# SCH_Navigation_Board_CapibaraZero_2024-0.net
KiCad netlist of a schematic drawn in EasyEDA
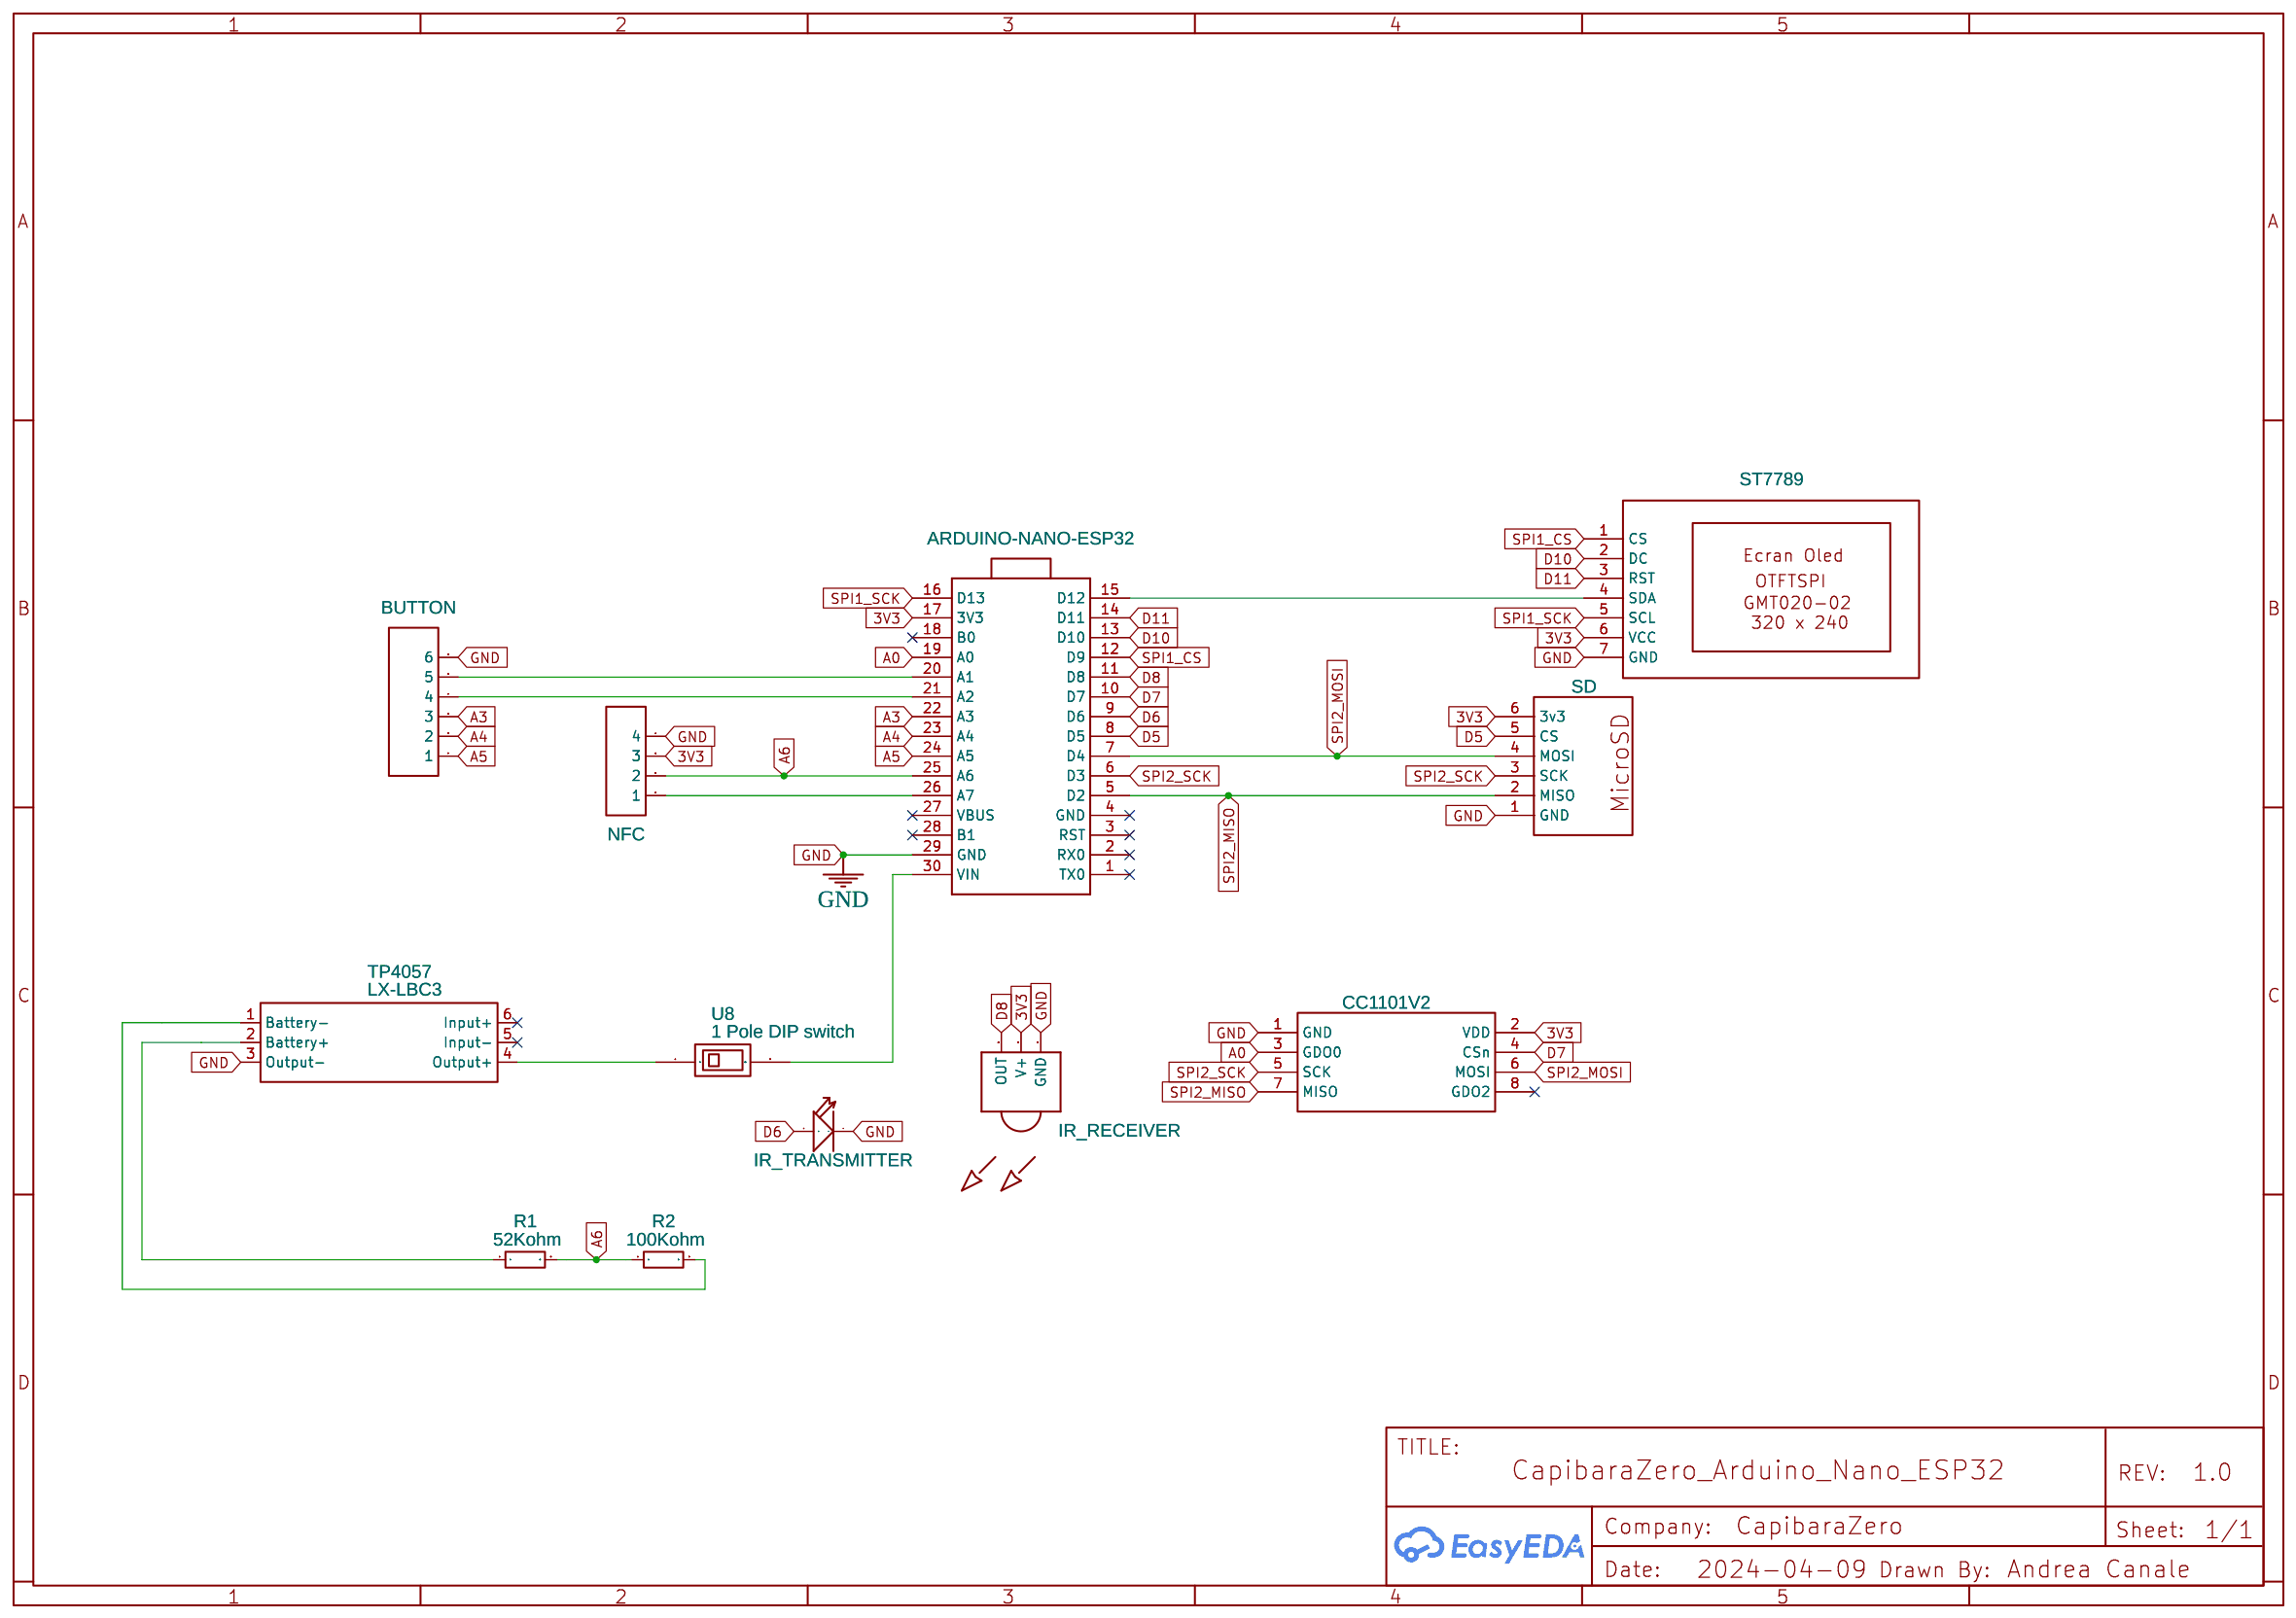
[diagram p0: MainScheme]
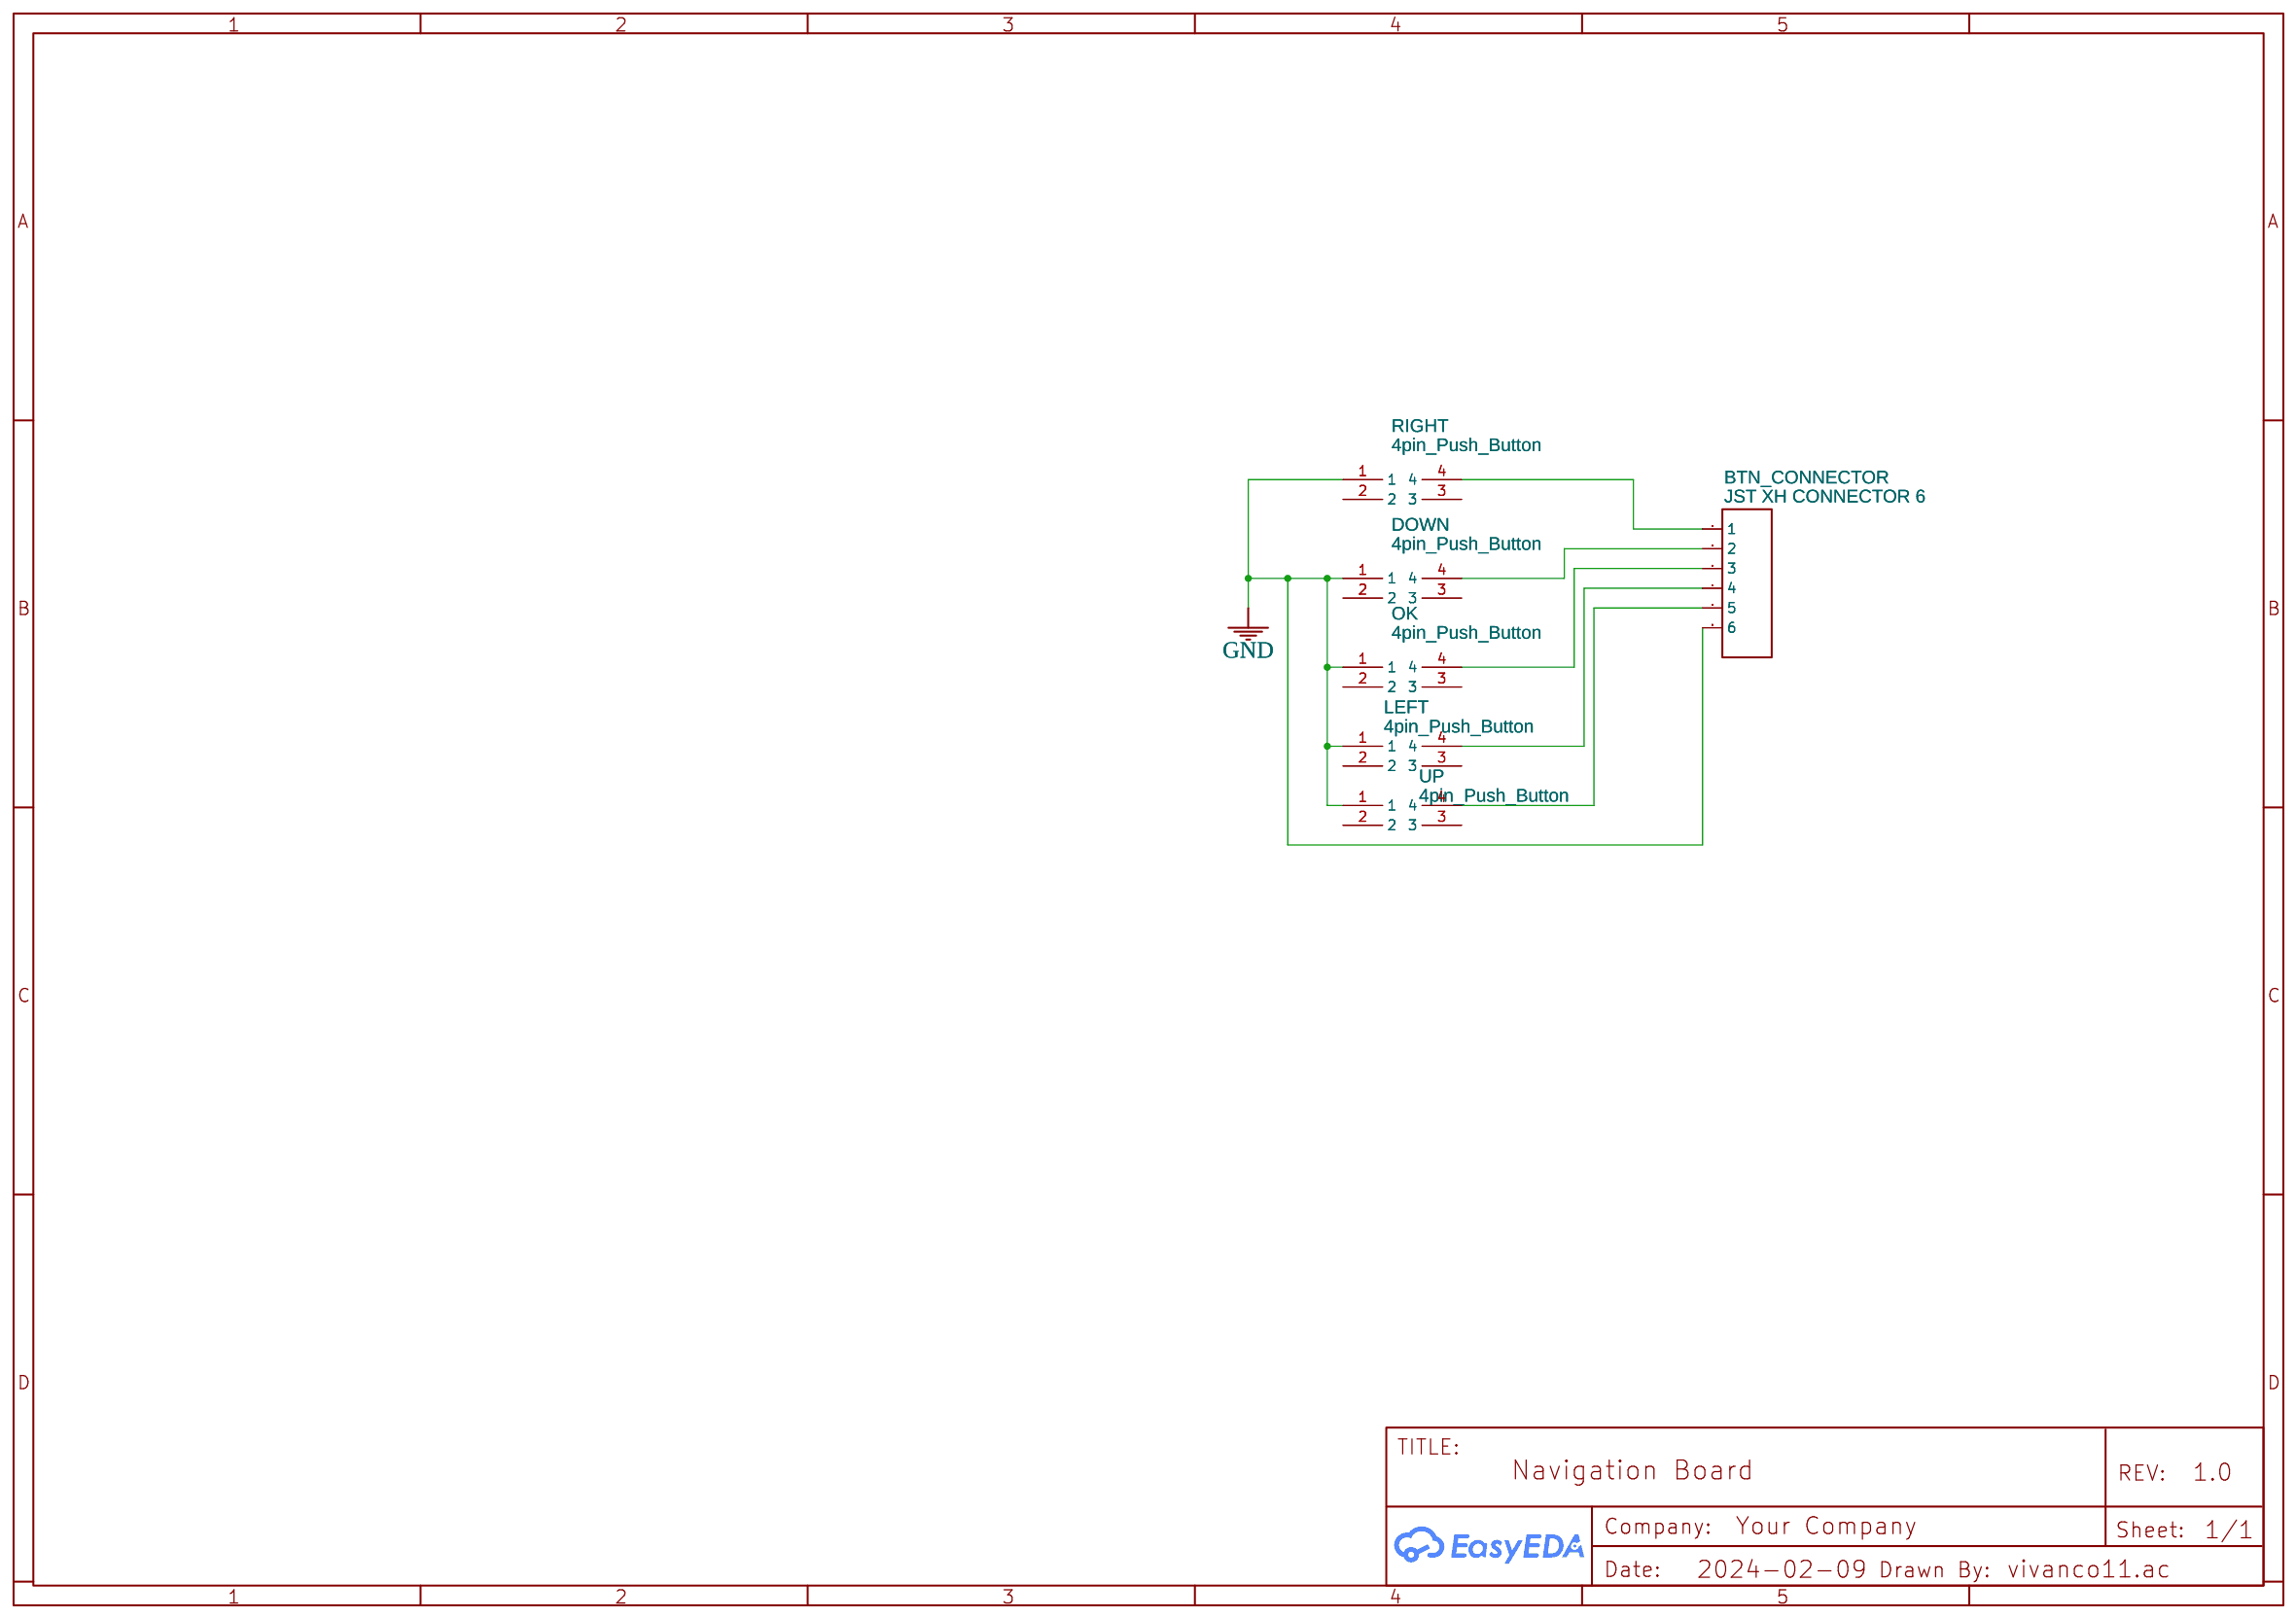
[diagram p1: Navigation_board]

(export (version "E")
  (design (tool "Eeschema 10.0.6"))
  (components
    (comp (ref "ARDUINO-NANO-ESP32")
      (value "ARDUINO-NANO-ESP32")
      (fields (field (name "Manufacturer") "Arduino"))
      (libsource (lib "") (part "ARDUINO-NANO-ESP32"))
    )
    (comp (ref "BUTTON")
      (value "BTN Connector")
      (fields (field (name "Manufacturer Part") "JST_XH CONNECTOR"))
      (libsource (lib "") (part "JST XH CONNECTOR 6"))
    )
    (comp (ref "CC1101V2")
      (value "CC1101 E07-M1101D")
      (fields
        (field (name "Manufacturer Part") "E07-M1101D-SMA")
        (field (name "Manufacturer") "Chengdu Ebyte Electronic Technology Co., Ltd.")
      )
      (libsource (lib "") (part "CC1101 E07-M1101D"))
    )
    (comp (ref "IR_RECEIVER") (value "IR Receiver") (libsource (lib "") (part "IR TRANSMITTER")))
    (comp (ref "IR_TRANSMITTER")
      (value "DIP-IR-LED-940NM(2P-D5MM)")
      (fields (field (name "Manufacturer Part") "IR523B-W60W1"))
      (libsource (lib "") (part "DIP-IR-LED-940NM(2P-D5MM)"))
    )
    (comp (ref "NFC")
      (value "NFC Connector")
      (fields (field (name "Manufacturer Part") "JST_XH CONNECTOR"))
      (libsource (lib "") (part "JST XH CONNECTOR 4"))
    )
    (comp (ref "R1")
      (value "52Kohm")
      (fields
        (field (name "Manufacturer Part") "EWWR0001J20R0T9")
        (field (name "Manufacturer") "ResistorToday")
      )
      (libsource (lib "") (part "Resistor Normal"))
    )
    (comp (ref "R2")
      (value "100Kohm")
      (fields
        (field (name "Manufacturer Part") "EWWR0001J20R0T9")
        (field (name "Manufacturer") "ResistorToday")
      )
      (libsource (lib "") (part "Resistor Normal"))
    )
    (comp (ref "SD") (value "MicroSDSPI") (libsource (lib "") (part "MicroSDSPI")))
    (comp (ref "ST7789")
      (value "ST7789_Display_320x240_SPI")
      (libsource (lib "") (part "ST7789_Display_320x240_SPI"))
    )
    (comp (ref "TP4057") (value "LX-LBC3") (libsource (lib "") (part "LX-LBC3")))
    (comp (ref "U8") (value "1 Pole DIP switch") (libsource (lib "") (part "1 Pole DIP switch")))
    (comp (ref "BTN_CONNECTOR")
      (value "JST XH CONNECTOR 6")
      (fields (field (name "Manufacturer Part") "JST_XH CONNECTOR"))
      (libsource (lib "") (part "JST XH CONNECTOR 6"))
    )
    (comp (ref "DOWN") (value "4pin_Push_Button") (libsource (lib "") (part "4pin_Push_Button_4")))
    (comp (ref "LEFT") (value "4pin_Push_Button") (libsource (lib "") (part "4pin_Push_Button")))
    (comp (ref "OK") (value "4pin_Push_Button") (libsource (lib "") (part "4pin_Push_Button_3")))
    (comp (ref "RIGHT") (value "4pin_Push_Button") (libsource (lib "") (part "4pin_Push_Button_1")))
    (comp (ref "UP") (value "4pin_Push_Button") (libsource (lib "") (part "4pin_Push_Button_2")))
  )
  (nets
    (net (code "1") (name "3V3") (class "Default")
      (node (ref "ARDUINO-NANO-ESP32") (pin "17") (pinfunction "3V3_17") (pintype "unspecified"))
      (node (ref "CC1101V2") (pin "2") (pinfunction "VDD_2") (pintype "unspecified"))
      (node (ref "IR_RECEIVER") (pin "VCC") (pinfunction "V+_VCC") (pintype "unspecified"))
      (node (ref "NFC") (pin "3") (pinfunction "3_3") (pintype "unspecified"))
      (node (ref "SD") (pin "6") (pinfunction "3v3_6") (pintype "unspecified"))
      (node (ref "ST7789") (pin "6") (pinfunction "VCC_6") (pintype "unspecified"))
    )
    (net (code "2") (name "A0") (class "Default")
      (node (ref "ARDUINO-NANO-ESP32") (pin "19") (pinfunction "A0_19") (pintype "unspecified"))
      (node (ref "CC1101V2") (pin "3") (pinfunction "GDO0_3") (pintype "unspecified"))
    )
    (net (code "3") (name "A3") (class "Default")
      (node (ref "ARDUINO-NANO-ESP32") (pin "22") (pinfunction "A3_22") (pintype "unspecified"))
      (node (ref "BUTTON") (pin "3") (pinfunction "3_3") (pintype "unspecified"))
    )
    (net (code "4") (name "A4") (class "Default")
      (node (ref "ARDUINO-NANO-ESP32") (pin "23") (pinfunction "A4_23") (pintype "unspecified"))
      (node (ref "BUTTON") (pin "2") (pinfunction "2_2") (pintype "unspecified"))
    )
    (net (code "5") (name "A5") (class "Default")
      (node (ref "ARDUINO-NANO-ESP32") (pin "24") (pinfunction "A5_24") (pintype "unspecified"))
      (node (ref "BUTTON") (pin "1") (pinfunction "1_1") (pintype "unspecified"))
    )
    (net (code "6") (name "A6") (class "Default")
      (node (ref "ARDUINO-NANO-ESP32") (pin "25") (pinfunction "A6_25") (pintype "unspecified"))
      (node (ref "NFC") (pin "2") (pinfunction "2_2") (pintype "unspecified"))
      (node (ref "R1") (pin "2") (pinfunction "2_2") (pintype "unspecified"))
      (node (ref "R2") (pin "1") (pinfunction "1_1") (pintype "unspecified"))
    )
    (net (code "7") (name "D5") (class "Default")
      (node (ref "ARDUINO-NANO-ESP32") (pin "8") (pinfunction "D5_8") (pintype "unspecified"))
      (node (ref "SD") (pin "5") (pinfunction "CS_5") (pintype "unspecified"))
    )
    (net (code "8") (name "D6") (class "Default")
      (node (ref "ARDUINO-NANO-ESP32") (pin "9") (pinfunction "D6_9") (pintype "unspecified"))
      (node (ref "IR_TRANSMITTER") (pin "+") (pinfunction "+_+") (pintype "unspecified"))
    )
    (net (code "9") (name "D7") (class "Default")
      (node (ref "ARDUINO-NANO-ESP32") (pin "10") (pinfunction "D7_10") (pintype "unspecified"))
      (node (ref "CC1101V2") (pin "4") (pinfunction "CSn_4") (pintype "unspecified"))
    )
    (net (code "10") (name "D8") (class "Default")
      (node (ref "ARDUINO-NANO-ESP32") (pin "11") (pinfunction "D8_11") (pintype "unspecified"))
      (node (ref "IR_RECEIVER") (pin "OUT") (pinfunction "OUT_OUT") (pintype "unspecified"))
    )
    (net (code "11") (name "D10") (class "Default")
      (node (ref "ARDUINO-NANO-ESP32") (pin "13") (pinfunction "D10_13") (pintype "unspecified"))
      (node (ref "ST7789") (pin "2") (pinfunction "DC_2") (pintype "unspecified"))
    )
    (net (code "12") (name "D11") (class "Default")
      (node (ref "ARDUINO-NANO-ESP32") (pin "14") (pinfunction "D11_14") (pintype "unspecified"))
      (node (ref "ST7789") (pin "3") (pinfunction "RST_3") (pintype "unspecified"))
    )
    (net (code "13") (name "GND") (class "Default")
      (node (ref "ARDUINO-NANO-ESP32") (pin "29") (pinfunction "GND_29") (pintype "unspecified"))
      (node (ref "BTN_CONNECTOR") (pin "6") (pinfunction "6_6") (pintype "unspecified"))
      (node (ref "BUTTON") (pin "6") (pinfunction "6_6") (pintype "unspecified"))
      (node (ref "CC1101V2") (pin "1") (pinfunction "GND_1") (pintype "unspecified"))
      (node (ref "DOWN") (pin "1") (pinfunction "1_1") (pintype "unspecified"))
      (node (ref "IR_RECEIVER") (pin "GND") (pinfunction "GND_GND") (pintype "unspecified"))
      (node (ref "IR_TRANSMITTER") (pin "-") (pinfunction "-_-") (pintype "unspecified"))
      (node (ref "LEFT") (pin "1") (pinfunction "1_1") (pintype "unspecified"))
      (node (ref "NFC") (pin "4") (pinfunction "4_4") (pintype "unspecified"))
      (node (ref "OK") (pin "1") (pinfunction "1_1") (pintype "unspecified"))
      (node (ref "RIGHT") (pin "1") (pinfunction "1_1") (pintype "unspecified"))
      (node (ref "SD") (pin "1") (pinfunction "GND_1") (pintype "unspecified"))
      (node (ref "ST7789") (pin "7") (pinfunction "GND_7") (pintype "unspecified"))
      (node (ref "TP4057") (pin "3") (pinfunction "Output-_3") (pintype "unspecified"))
      (node (ref "UP") (pin "1") (pinfunction "1_1") (pintype "unspecified"))
    )
    (net (code "14") (name "Net-(ARDUINO-NANO-ESP32-A1)") (class "Default")
      (node (ref "ARDUINO-NANO-ESP32") (pin "20") (pinfunction "A1_20") (pintype "unspecified"))
      (node (ref "BUTTON") (pin "5") (pinfunction "5_5") (pintype "unspecified"))
    )
    (net (code "15") (name "Net-(ARDUINO-NANO-ESP32-A2)") (class "Default")
      (node (ref "ARDUINO-NANO-ESP32") (pin "21") (pinfunction "A2_21") (pintype "unspecified"))
      (node (ref "BUTTON") (pin "4") (pinfunction "4_4") (pintype "unspecified"))
    )
    (net (code "16") (name "Net-(ARDUINO-NANO-ESP32-A7)") (class "Default")
      (node (ref "ARDUINO-NANO-ESP32") (pin "26") (pinfunction "A7_26") (pintype "unspecified"))
      (node (ref "NFC") (pin "1") (pinfunction "1_1") (pintype "unspecified"))
    )
    (net (code "17") (name "Net-(ARDUINO-NANO-ESP32-D12)") (class "Default")
      (node (ref "ARDUINO-NANO-ESP32") (pin "15") (pinfunction "D12_15") (pintype "unspecified"))
      (node (ref "ST7789") (pin "4") (pinfunction "SDA_4") (pintype "unspecified"))
    )
    (net (code "18") (name "Net-(ARDUINO-NANO-ESP32-VIN)") (class "Default")
      (node (ref "ARDUINO-NANO-ESP32") (pin "30") (pinfunction "VIN_30") (pintype "unspecified"))
      (node (ref "U8") (pin "2") (pinfunction "OUT_2") (pintype "unspecified"))
    )
    (net (code "19") (name "Net-(BTN_CONNECTOR-Pad1)") (class "Default")
      (node (ref "BTN_CONNECTOR") (pin "1") (pinfunction "1_1") (pintype "unspecified"))
      (node (ref "RIGHT") (pin "4") (pinfunction "4_4") (pintype "unspecified"))
    )
    (net (code "20") (name "Net-(BTN_CONNECTOR-Pad2)") (class "Default")
      (node (ref "BTN_CONNECTOR") (pin "2") (pinfunction "2_2") (pintype "unspecified"))
      (node (ref "DOWN") (pin "4") (pinfunction "4_4") (pintype "unspecified"))
    )
    (net (code "21") (name "Net-(BTN_CONNECTOR-Pad3)") (class "Default")
      (node (ref "BTN_CONNECTOR") (pin "3") (pinfunction "3_3") (pintype "unspecified"))
      (node (ref "OK") (pin "4") (pinfunction "4_4") (pintype "unspecified"))
    )
    (net (code "22") (name "Net-(BTN_CONNECTOR-Pad4)") (class "Default")
      (node (ref "BTN_CONNECTOR") (pin "4") (pinfunction "4_4") (pintype "unspecified"))
      (node (ref "LEFT") (pin "4") (pinfunction "4_4") (pintype "unspecified"))
    )
    (net (code "23") (name "Net-(BTN_CONNECTOR-Pad5)") (class "Default")
      (node (ref "BTN_CONNECTOR") (pin "5") (pinfunction "5_5") (pintype "unspecified"))
      (node (ref "UP") (pin "4") (pinfunction "4_4") (pintype "unspecified"))
    )
    (net (code "24") (name "Net-(TP4057-Battery+)") (class "Default")
      (node (ref "R1") (pin "1") (pinfunction "1_1") (pintype "unspecified"))
      (node (ref "TP4057") (pin "2") (pinfunction "Battery+_2") (pintype "unspecified"))
    )
    (net (code "25") (name "Net-(TP4057-Battery-)") (class "Default")
      (node (ref "R2") (pin "2") (pinfunction "2_2") (pintype "unspecified"))
      (node (ref "TP4057") (pin "1") (pinfunction "Battery-_1") (pintype "unspecified"))
    )
    (net (code "26") (name "Net-(TP4057-Output+)") (class "Default")
      (node (ref "TP4057") (pin "4") (pinfunction "Output+_4") (pintype "unspecified"))
      (node (ref "U8") (pin "1") (pinfunction "IN_1") (pintype "unspecified"))
    )
    (net (code "27") (name "SPI1_CS") (class "Default")
      (node (ref "ARDUINO-NANO-ESP32") (pin "12") (pinfunction "D9_12") (pintype "unspecified"))
      (node (ref "ST7789") (pin "1") (pinfunction "CS_1") (pintype "unspecified"))
    )
    (net (code "28") (name "SPI1_SCK") (class "Default")
      (node (ref "ARDUINO-NANO-ESP32") (pin "16") (pinfunction "D13_16") (pintype "unspecified"))
      (node (ref "ST7789") (pin "5") (pinfunction "SCL_5") (pintype "unspecified"))
    )
    (net (code "29") (name "SPI2_MISO") (class "Default")
      (node (ref "ARDUINO-NANO-ESP32") (pin "5") (pinfunction "D2_5") (pintype "unspecified"))
      (node (ref "CC1101V2") (pin "7") (pinfunction "MISO_7") (pintype "unspecified"))
      (node (ref "SD") (pin "2") (pinfunction "MISO_2") (pintype "unspecified"))
    )
    (net (code "30") (name "SPI2_MOSI") (class "Default")
      (node (ref "ARDUINO-NANO-ESP32") (pin "7") (pinfunction "D4_7") (pintype "unspecified"))
      (node (ref "CC1101V2") (pin "6") (pinfunction "MOSI_6") (pintype "unspecified"))
      (node (ref "SD") (pin "4") (pinfunction "MOSI_4") (pintype "unspecified"))
    )
    (net (code "31") (name "SPI2_SCK") (class "Default")
      (node (ref "ARDUINO-NANO-ESP32") (pin "6") (pinfunction "D3_6") (pintype "unspecified"))
      (node (ref "CC1101V2") (pin "5") (pinfunction "SCK_5") (pintype "unspecified"))
      (node (ref "SD") (pin "3") (pinfunction "SCK_3") (pintype "unspecified"))
    )
    (net (code "32") (name "unconnected-(ARDUINO-NANO-ESP32-B0-Pad18)") (class "Default")
      (node (ref "ARDUINO-NANO-ESP32") (pin "18") (pinfunction "B0_18") (pintype "unspecified+no_connect"))
    )
    (net (code "33") (name "unconnected-(ARDUINO-NANO-ESP32-B1-Pad28)") (class "Default")
      (node (ref "ARDUINO-NANO-ESP32") (pin "28") (pinfunction "B1_28") (pintype "unspecified+no_connect"))
    )
    (net (code "34") (name "unconnected-(ARDUINO-NANO-ESP32-GND-Pad4)") (class "Default")
      (node (ref "ARDUINO-NANO-ESP32") (pin "4") (pinfunction "GND_4") (pintype "unspecified+no_connect"))
    )
    (net (code "35") (name "unconnected-(ARDUINO-NANO-ESP32-RST-Pad3)") (class "Default")
      (node (ref "ARDUINO-NANO-ESP32") (pin "3") (pinfunction "RST_3") (pintype "unspecified+no_connect"))
    )
    (net (code "36") (name "unconnected-(ARDUINO-NANO-ESP32-RX0-Pad2)") (class "Default")
      (node (ref "ARDUINO-NANO-ESP32") (pin "2") (pinfunction "RX0_2") (pintype "unspecified+no_connect"))
    )
    (net (code "37") (name "unconnected-(ARDUINO-NANO-ESP32-TX0-Pad1)") (class "Default")
      (node (ref "ARDUINO-NANO-ESP32") (pin "1") (pinfunction "TX0_1") (pintype "unspecified+no_connect"))
    )
    (net (code "38") (name "unconnected-(ARDUINO-NANO-ESP32-VBUS-Pad27)") (class "Default")
      (node (ref "ARDUINO-NANO-ESP32") (pin "27") (pinfunction "VBUS_27") (pintype "unspecified+no_connect"))
    )
    (net (code "39") (name "unconnected-(CC1101V2-GDO2-Pad8)") (class "Default")
      (node (ref "CC1101V2") (pin "8") (pinfunction "GDO2_8") (pintype "unspecified+no_connect"))
    )
    (net (code "40") (name "unconnected-(DOWN-Pad2)") (class "Default")
      (node (ref "DOWN") (pin "2") (pinfunction "2_2") (pintype "unspecified"))
    )
    (net (code "41") (name "unconnected-(DOWN-Pad3)") (class "Default")
      (node (ref "DOWN") (pin "3") (pinfunction "3_3") (pintype "unspecified"))
    )
    (net (code "42") (name "unconnected-(LEFT-Pad2)") (class "Default")
      (node (ref "LEFT") (pin "2") (pinfunction "2_2") (pintype "unspecified"))
    )
    (net (code "43") (name "unconnected-(LEFT-Pad3)") (class "Default")
      (node (ref "LEFT") (pin "3") (pinfunction "3_3") (pintype "unspecified"))
    )
    (net (code "44") (name "unconnected-(OK-Pad2)") (class "Default")
      (node (ref "OK") (pin "2") (pinfunction "2_2") (pintype "unspecified"))
    )
    (net (code "45") (name "unconnected-(OK-Pad3)") (class "Default")
      (node (ref "OK") (pin "3") (pinfunction "3_3") (pintype "unspecified"))
    )
    (net (code "46") (name "unconnected-(RIGHT-Pad2)") (class "Default")
      (node (ref "RIGHT") (pin "2") (pinfunction "2_2") (pintype "unspecified"))
    )
    (net (code "47") (name "unconnected-(RIGHT-Pad3)") (class "Default")
      (node (ref "RIGHT") (pin "3") (pinfunction "3_3") (pintype "unspecified"))
    )
    (net (code "48") (name "unconnected-(TP4057-Input+-Pad6)") (class "Default")
      (node (ref "TP4057") (pin "6") (pinfunction "Input+_6") (pintype "unspecified+no_connect"))
    )
    (net (code "49") (name "unconnected-(TP4057-Input--Pad5)") (class "Default")
      (node (ref "TP4057") (pin "5") (pinfunction "Input-_5") (pintype "unspecified+no_connect"))
    )
    (net (code "50") (name "unconnected-(UP-Pad2)") (class "Default")
      (node (ref "UP") (pin "2") (pinfunction "2_2") (pintype "unspecified"))
    )
    (net (code "51") (name "unconnected-(UP-Pad3)") (class "Default")
      (node (ref "UP") (pin "3") (pinfunction "3_3") (pintype "unspecified"))
    )
  )
)
